# Blackbox_BauhallenUhr_Schematic.net
KiCad netlist of a schematic drawn in Altium Designer
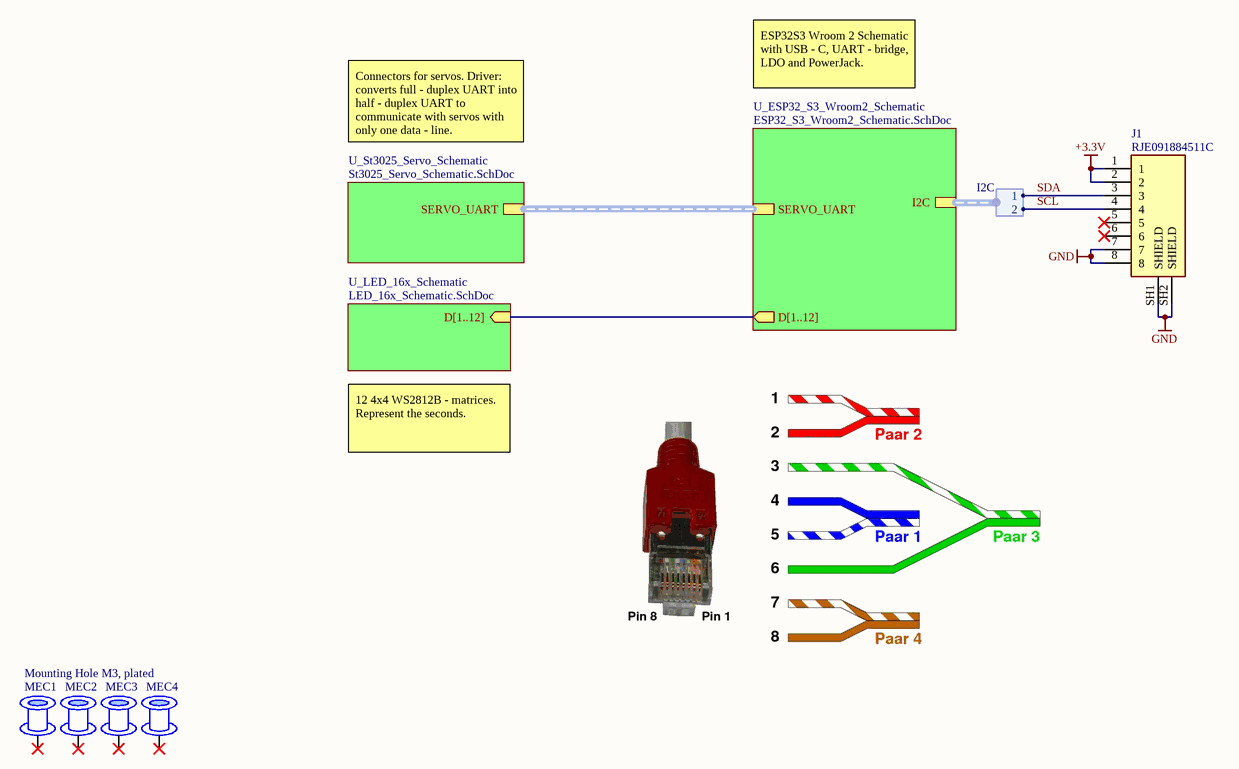
[diagram p0: Blackbox_BauhallenUhr_Schematic.SchDoc]

(export (version "E")
  (design (tool "Eeschema 10.0.6"))
  (components
    (comp (ref "J1")
      (value "RJE091884511C")
      (footprint "PCB_Altium_Library_Manuel:RJ45")
      (description "Jack Modular Connector 8p8c (RJ45, Ethernet) 90Â° Angle (Right) Shielded Cat3.")
      (fields (field (name "MF") "Amphenol ICC (Commercial Products)"))
      (libsource (lib "Schematic_Altium_Library_Manuel") (part "RJ45"))
    )
    (comp (ref "MEC1")
      (value "Mounting Hole M3, plated")
      (footprint "PCB_Altium_Library_Manuel:Mounting Hole M3, plated")
      (description "Mounting Hole for M3 Screw, plated to connect signal")
      (libsource (lib "Schematic_Altium_Library_Manuel") (part "Mounting Hole M3, plated"))
    )
    (comp (ref "MEC2")
      (value "Mounting Hole M3, plated")
      (footprint "PCB_Altium_Library_Manuel:Mounting Hole M3, plated")
      (description "Mounting Hole for M3 Screw, plated to connect signal")
      (libsource (lib "Schematic_Altium_Library_Manuel") (part "Mounting Hole M3, plated"))
    )
    (comp (ref "MEC3")
      (value "Mounting Hole M3, plated")
      (footprint "PCB_Altium_Library_Manuel:Mounting Hole M3, plated")
      (description "Mounting Hole for M3 Screw, plated to connect signal")
      (libsource (lib "Schematic_Altium_Library_Manuel") (part "Mounting Hole M3, plated"))
    )
    (comp (ref "MEC4")
      (value "Mounting Hole M3, plated")
      (footprint "PCB_Altium_Library_Manuel:Mounting Hole M3, plated")
      (description "Mounting Hole for M3 Screw, plated to connect signal")
      (libsource (lib "Schematic_Altium_Library_Manuel") (part "Mounting Hole M3, plated"))
    )
  )
  (nets
    (net (code "2") (name "+3.3V") (class "Default")
      (node (ref "J1") (pin "1") (pinfunction "1_1") (pintype "passive"))
      (node (ref "J1") (pin "2") (pinfunction "2_2") (pintype "passive"))
    )
    (net (code "4") (name "/SCL") (class "Default")
      (node (ref "J1") (pin "4") (pinfunction "4_4") (pintype "passive"))
    )
    (net (code "5") (name "/SDA") (class "Default")
      (node (ref "J1") (pin "3") (pinfunction "3_3") (pintype "passive"))
    )
    (net (code "8") (name "GND") (class "Default")
      (node (ref "J1") (pin "7") (pinfunction "7_7") (pintype "passive"))
      (node (ref "J1") (pin "8") (pinfunction "8_8") (pintype "passive"))
      (node (ref "J1") (pin "SH1") (pinfunction "SHIELD_SH1") (pintype "passive"))
      (node (ref "J1") (pin "SH2") (pinfunction "SHIELD_SH2") (pintype "passive"))
    )
    (net (code "9") (name "unconnected-(J1-Pad5)") (class "Default")
      (node (ref "J1") (pin "5") (pinfunction "5_5") (pintype "passive+no_connect"))
    )
    (net (code "10") (name "unconnected-(J1-Pad6)") (class "Default")
      (node (ref "J1") (pin "6") (pinfunction "6_6") (pintype "passive+no_connect"))
    )
    (net (code "11") (name "unconnected-(MEC1-Pad1)") (class "Default")
      (node (ref "MEC1") (pin "1") (pinfunction "1_1") (pintype "passive+no_connect"))
    )
    (net (code "12") (name "unconnected-(MEC2-Pad1)") (class "Default")
      (node (ref "MEC2") (pin "1") (pinfunction "1_1") (pintype "passive+no_connect"))
    )
    (net (code "13") (name "unconnected-(MEC3-Pad1)") (class "Default")
      (node (ref "MEC3") (pin "1") (pinfunction "1_1") (pintype "passive+no_connect"))
    )
    (net (code "14") (name "unconnected-(MEC4-Pad1)") (class "Default")
      (node (ref "MEC4") (pin "1") (pinfunction "1_1") (pintype "passive+no_connect"))
    )
  )
)
